# AccBreakout.net
KiCad netlist of a schematic drawn in EAGLE
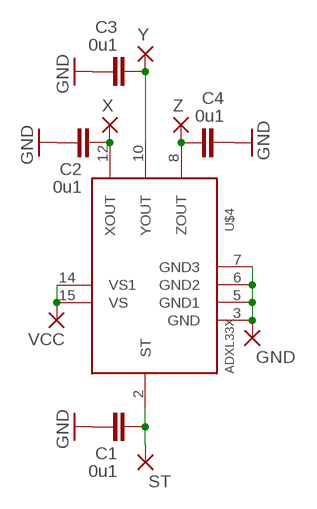
[diagram p0: schematic, sheet 1]

(export (version "E")
  (design (tool "Eeschema 10.0.6"))
  (components
    (comp (ref "C1")
      (value "0u1")
      (footprint "eagle-import:0402-CAP")
      (libsource (lib "eagle-import") (part "CAP0402-CAP"))
    )
    (comp (ref "C2")
      (value "0u1")
      (footprint "eagle-import:0402-CAP")
      (libsource (lib "eagle-import") (part "CAP0402-CAP"))
    )
    (comp (ref "C3")
      (value "0u1")
      (footprint "eagle-import:0402-CAP")
      (libsource (lib "eagle-import") (part "CAP0402-CAP"))
    )
    (comp (ref "C4")
      (value "0u1")
      (footprint "eagle-import:0402-CAP")
      (libsource (lib "eagle-import") (part "CAP0402-CAP"))
    )
    (comp (ref "GND")
      (value "2,15/1,0")
      (footprint "eagle-import:2,15_1,0")
      (libsource (lib "eagle-import") (part "2,15/1,0"))
    )
    (comp (ref "ST")
      (value "2,15/1,0")
      (footprint "eagle-import:2,15_1,0")
      (libsource (lib "eagle-import") (part "2,15/1,0"))
    )
    (comp (ref "U$4")
      (value "ADXL33X")
      (footprint "eagle-import:16LCSP")
      (libsource (lib "eagle-import") (part "ADXL33X"))
    )
    (comp (ref "VCC")
      (value "2,15/1,0")
      (footprint "eagle-import:2,15_1,0")
      (libsource (lib "eagle-import") (part "2,15/1,0"))
    )
    (comp (ref "X")
      (value "2,15/1,0")
      (footprint "eagle-import:2,15_1,0")
      (libsource (lib "eagle-import") (part "2,15/1,0"))
    )
    (comp (ref "Y")
      (value "2,15/1,0")
      (footprint "eagle-import:2,15_1,0")
      (libsource (lib "eagle-import") (part "2,15/1,0"))
    )
    (comp (ref "Z")
      (value "2,15/1,0")
      (footprint "eagle-import:2,15_1,0")
      (libsource (lib "eagle-import") (part "2,15/1,0"))
    )
  )
  (nets
    (net (code "1") (name "GND") (class "Default")
      (node (ref "C1") (pin "1") (pinfunction "1_1") (pintype "passive"))
      (node (ref "C2") (pin "1") (pinfunction "1_1") (pintype "passive"))
      (node (ref "C3") (pin "1") (pinfunction "1_1") (pintype "passive"))
      (node (ref "C4") (pin "2") (pinfunction "2_2") (pintype "passive"))
      (node (ref "GND") (pin "1") (pinfunction "P_1") (pintype "passive"))
      (node (ref "U$4") (pin "3") (pinfunction "GND_3") (pintype "power_in"))
      (node (ref "U$4") (pin "5") (pinfunction "GND1_5") (pintype "power_in"))
      (node (ref "U$4") (pin "6") (pinfunction "GND2_6") (pintype "power_in"))
      (node (ref "U$4") (pin "7") (pinfunction "GND3_7") (pintype "power_in"))
    )
    (net (code "2") (name "Net-(ST-P)") (class "Default")
      (node (ref "C1") (pin "2") (pinfunction "2_2") (pintype "passive"))
      (node (ref "ST") (pin "1") (pinfunction "P_1") (pintype "passive"))
      (node (ref "U$4") (pin "2") (pinfunction "ST_2") (pintype "input"))
    )
    (net (code "3") (name "Net-(U$4-VS)") (class "Default")
      (node (ref "U$4") (pin "14") (pinfunction "VS1_14") (pintype "power_in"))
      (node (ref "U$4") (pin "15") (pinfunction "VS_15") (pintype "power_in"))
      (node (ref "VCC") (pin "1") (pinfunction "P_1") (pintype "passive"))
    )
    (net (code "4") (name "Net-(U$4-XOUT)") (class "Default")
      (node (ref "C2") (pin "2") (pinfunction "2_2") (pintype "passive"))
      (node (ref "U$4") (pin "12") (pinfunction "XOUT_12") (pintype "output"))
      (node (ref "X") (pin "1") (pinfunction "P_1") (pintype "passive"))
    )
    (net (code "5") (name "Net-(U$4-YOUT)") (class "Default")
      (node (ref "C3") (pin "2") (pinfunction "2_2") (pintype "passive"))
      (node (ref "U$4") (pin "10") (pinfunction "YOUT_10") (pintype "output"))
      (node (ref "Y") (pin "1") (pinfunction "P_1") (pintype "passive"))
    )
    (net (code "6") (name "Net-(U$4-ZOUT)") (class "Default")
      (node (ref "C4") (pin "1") (pinfunction "1_1") (pintype "passive"))
      (node (ref "U$4") (pin "8") (pinfunction "ZOUT_8") (pintype "output"))
      (node (ref "Z") (pin "1") (pinfunction "P_1") (pintype "passive"))
    )
  )
)
